# digital_noise_gen.net
KiCad netlist of a schematic drawn in EAGLE
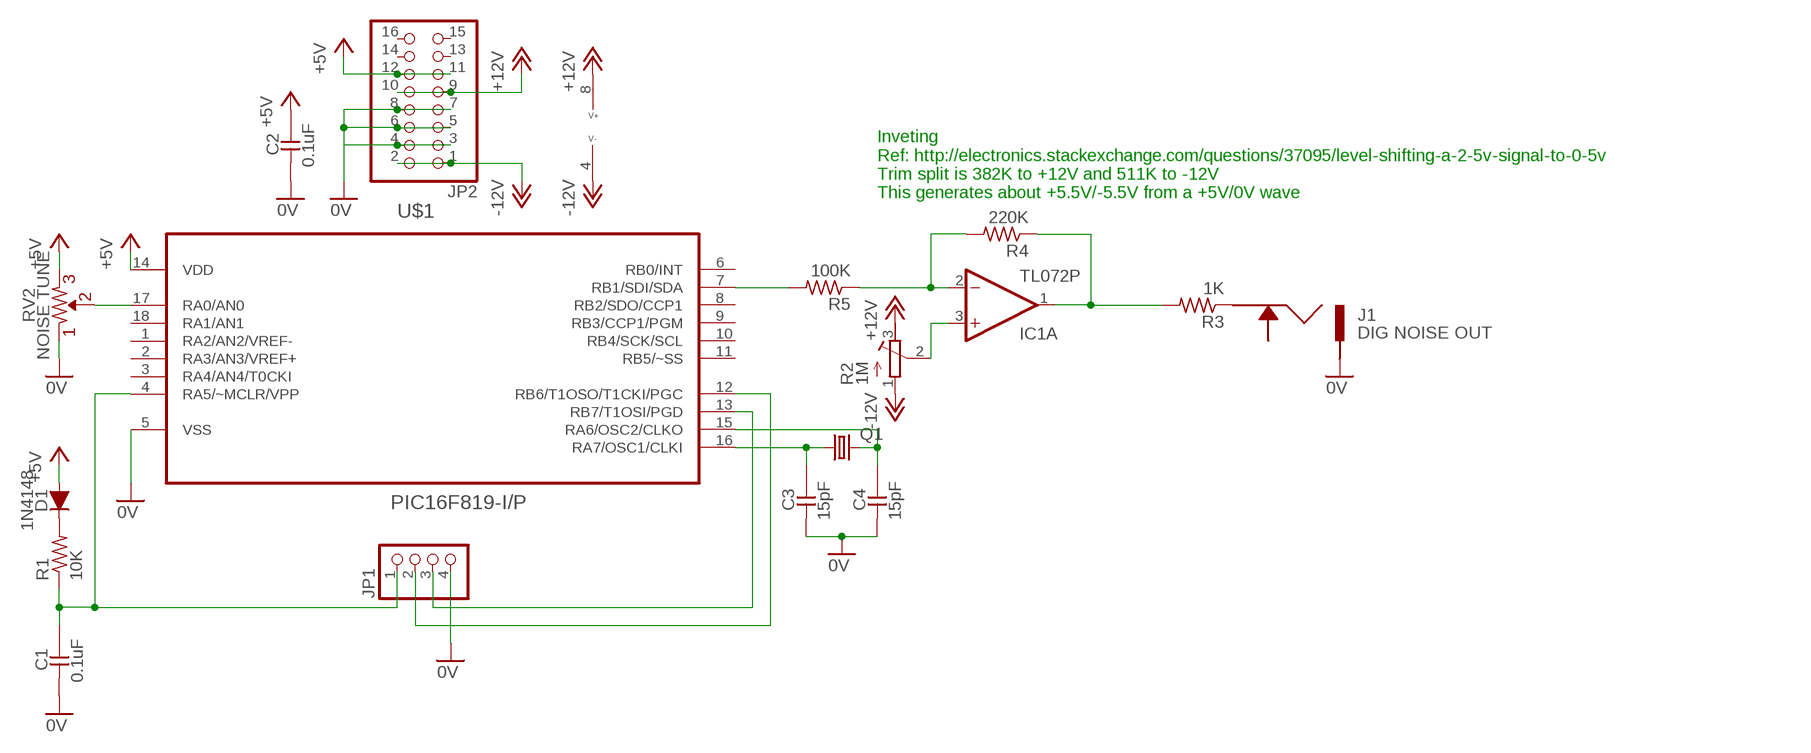
[diagram p0: schematic, sheet 1]

(export (version "E")
  (design (tool "Eeschema 10.0.6"))
  (components
    (comp (ref "C1")
      (value "0.1uF")
      (footprint "eagle-import:C025-024X044")
      (libsource (lib "eagle-import") (part "CC-US025-024X044"))
    )
    (comp (ref "C2")
      (value "0.1uF")
      (footprint "eagle-import:C025-024X044")
      (libsource (lib "eagle-import") (part "CC-US025-024X044"))
    )
    (comp (ref "C3")
      (value "15pF")
      (footprint "eagle-import:C025-024X044")
      (libsource (lib "eagle-import") (part "CC-US025-024X044"))
    )
    (comp (ref "C4")
      (value "15pF")
      (footprint "eagle-import:C025-024X044")
      (libsource (lib "eagle-import") (part "CC-US025-024X044"))
    )
    (comp (ref "D1")
      (value "1N4148")
      (footprint "eagle-import:DO35-7")
      (libsource (lib "eagle-import") (part "1N4148"))
    )
    (comp (ref "IC1")
      (value "TL072P")
      (footprint "eagle-import:DIL08")
      (libsource (lib "eagle-import") (part "TL072P"))
    )
    (comp (ref "J1")
      (value "DIG NOISE OUT")
      (footprint "eagle-import:ACJM-MV35-2S")
      (libsource (lib "eagle-import") (part "ACJM-MV35-2S"))
    )
    (comp (ref "JP1")
      (value "PINHD-1X4")
      (footprint "eagle-import:1X04")
      (libsource (lib "eagle-import") (part "PINHD-1X4"))
    )
    (comp (ref "JP2")
      (value "PINHD-2X8")
      (footprint "eagle-import:2X08")
      (libsource (lib "eagle-import") (part "PINHD-2X8"))
    )
    (comp (ref "Q1")
      (value "CRYSTALHC49S")
      (footprint "eagle-import:HC49_S")
      (libsource (lib "eagle-import") (part "CRYSTALHC49S"))
    )
    (comp (ref "R1")
      (value "10K")
      (footprint "eagle-import:0207_7")
      (libsource (lib "eagle-import") (part "R-US_0207/7"))
    )
    (comp (ref "R2")
      (value "1M")
      (footprint "eagle-import:RTRIM3339P")
      (libsource (lib "eagle-import") (part "R-TRIMM3339P"))
    )
    (comp (ref "R3")
      (value "1K")
      (footprint "eagle-import:0207_7")
      (libsource (lib "eagle-import") (part "R-US_0207/7"))
    )
    (comp (ref "R4")
      (value "220K")
      (footprint "eagle-import:0207_7")
      (libsource (lib "eagle-import") (part "R-US_0207/7"))
    )
    (comp (ref "R5")
      (value "100K")
      (footprint "eagle-import:0207_7")
      (libsource (lib "eagle-import") (part "R-US_0207/7"))
    )
    (comp (ref "RV2")
      (value "NOISE TUNE")
      (footprint "eagle-import:R-VAR")
      (libsource (lib "eagle-import") (part "R-VAR"))
    )
    (comp (ref "U$1")
      (value "PIC16F819-I/P")
      (footprint "eagle-import:DIP254P762X432-18")
      (libsource (lib "eagle-import") (part "PIC16F819-I/P"))
    )
  )
  (nets
    (net (code "1") (name "+5V") (class "Default")
      (node (ref "C2") (pin "1") (pinfunction "1_1") (pintype "passive"))
      (node (ref "D1") (pin "A") (pinfunction "A_A") (pintype "passive"))
      (node (ref "JP2") (pin "11") (pinfunction "11_11") (pintype "passive"))
      (node (ref "JP2") (pin "12") (pinfunction "12_12") (pintype "passive"))
      (node (ref "RV2") (pin "R2") (pinfunction "2_R2") (pintype "passive"))
      (node (ref "U$1") (pin "14") (pinfunction "VDD_14") (pintype "power_in"))
    )
    (net (code "2") (name "+12V") (class "Default")
      (node (ref "IC1") (pin "8") (pinfunction "V+_8") (pintype "power_in"))
      (node (ref "JP2") (pin "10") (pinfunction "10_10") (pintype "passive"))
      (node (ref "JP2") (pin "9") (pinfunction "9_9") (pintype "passive"))
      (node (ref "R2") (pin "3") (pinfunction "E_3") (pintype "passive"))
    )
    (net (code "3") (name "-12V") (class "Default")
      (node (ref "IC1") (pin "4") (pinfunction "V-_4") (pintype "power_in"))
      (node (ref "JP2") (pin "1") (pinfunction "1_1") (pintype "passive"))
      (node (ref "JP2") (pin "2") (pinfunction "2_2") (pintype "passive"))
      (node (ref "R2") (pin "1") (pinfunction "A_1") (pintype "passive"))
    )
    (net (code "4") (name "0V") (class "Default")
      (node (ref "C1") (pin "2") (pinfunction "2_2") (pintype "passive"))
      (node (ref "C2") (pin "2") (pinfunction "2_2") (pintype "passive"))
      (node (ref "C3") (pin "2") (pinfunction "2_2") (pintype "passive"))
      (node (ref "C4") (pin "2") (pinfunction "2_2") (pintype "passive"))
      (node (ref "J1") (pin "P$1") (pinfunction "P$1_P$1") (pintype "bidirectional"))
      (node (ref "JP1") (pin "4") (pinfunction "4_4") (pintype "passive"))
      (node (ref "JP2") (pin "3") (pinfunction "3_3") (pintype "passive"))
      (node (ref "JP2") (pin "4") (pinfunction "4_4") (pintype "passive"))
      (node (ref "JP2") (pin "5") (pinfunction "5_5") (pintype "passive"))
      (node (ref "JP2") (pin "6") (pinfunction "6_6") (pintype "passive"))
      (node (ref "JP2") (pin "7") (pinfunction "7_7") (pintype "passive"))
      (node (ref "JP2") (pin "8") (pinfunction "8_8") (pintype "passive"))
      (node (ref "RV2") (pin "R1") (pinfunction "1_R1") (pintype "passive"))
      (node (ref "U$1") (pin "5") (pinfunction "VSS_5") (pintype "passive"))
    )
    (net (code "5") (name "Net-(D1-PadC)") (class "Default")
      (node (ref "D1") (pin "C") (pinfunction "C_C") (pintype "passive"))
      (node (ref "R1") (pin "2") (pinfunction "2_2") (pintype "passive"))
    )
    (net (code "6") (name "Net-(IC1A-+IN)") (class "Default")
      (node (ref "IC1") (pin "3") (pinfunction "+IN_3") (pintype "input"))
      (node (ref "R2") (pin "2") (pinfunction "S_2") (pintype "passive"))
    )
    (net (code "7") (name "Net-(IC1A--IN)") (class "Default")
      (node (ref "IC1") (pin "2") (pinfunction "-IN_2") (pintype "input"))
      (node (ref "R4") (pin "2") (pinfunction "2_2") (pintype "passive"))
      (node (ref "R5") (pin "1") (pinfunction "1_1") (pintype "passive"))
    )
    (net (code "8") (name "Net-(IC1A-OUT)") (class "Default")
      (node (ref "IC1") (pin "1") (pinfunction "OUT_1") (pintype "output"))
      (node (ref "R3") (pin "2") (pinfunction "2_2") (pintype "passive"))
      (node (ref "R4") (pin "1") (pinfunction "1_1") (pintype "passive"))
    )
    (net (code "9") (name "Net-(J1-P$2)") (class "Default")
      (node (ref "J1") (pin "P$3") (pinfunction "P$2_P$3") (pintype "bidirectional"))
      (node (ref "R3") (pin "1") (pinfunction "1_1") (pintype "passive"))
    )
    (net (code "10") (name "Net-(RV2-P$1)") (class "Default")
      (node (ref "RV2") (pin "VAR") (pinfunction "P$1_VAR") (pintype "passive"))
      (node (ref "U$1") (pin "17") (pinfunction "RA0/AN0_17") (pintype "bidirectional"))
    )
    (net (code "11") (name "Net-(U$1-RA5{slash}~{MCLR{slash}VPP})") (class "Default")
      (node (ref "C1") (pin "1") (pinfunction "1_1") (pintype "passive"))
      (node (ref "JP1") (pin "1") (pinfunction "1_1") (pintype "passive"))
      (node (ref "R1") (pin "1") (pinfunction "1_1") (pintype "passive"))
      (node (ref "U$1") (pin "4") (pinfunction "RA5/~{MCLR/VPP}_4") (pintype "input"))
    )
    (net (code "12") (name "Net-(U$1-RA6{slash}OSC2{slash}CLKO)") (class "Default")
      (node (ref "C4") (pin "1") (pinfunction "1_1") (pintype "passive"))
      (node (ref "Q1") (pin "2") (pinfunction "2_2") (pintype "passive"))
      (node (ref "U$1") (pin "15") (pinfunction "RA6/OSC2/CLKO_15") (pintype "bidirectional"))
    )
    (net (code "13") (name "Net-(U$1-RA7{slash}OSC1{slash}CLKI)") (class "Default")
      (node (ref "C3") (pin "1") (pinfunction "1_1") (pintype "passive"))
      (node (ref "Q1") (pin "1") (pinfunction "1_1") (pintype "passive"))
      (node (ref "U$1") (pin "16") (pinfunction "RA7/OSC1/CLKI_16") (pintype "bidirectional"))
    )
    (net (code "14") (name "Net-(U$1-RB1{slash}SDI{slash}SDA)") (class "Default")
      (node (ref "R5") (pin "2") (pinfunction "2_2") (pintype "passive"))
      (node (ref "U$1") (pin "7") (pinfunction "RB1/SDI/SDA_7") (pintype "bidirectional"))
    )
    (net (code "15") (name "Net-(U$1-RB6{slash}T1OSO{slash}T1CKI{slash}PGC)") (class "Default")
      (node (ref "JP1") (pin "2") (pinfunction "2_2") (pintype "passive"))
      (node (ref "U$1") (pin "12") (pinfunction "RB6/T1OSO/T1CKI/PGC_12") (pintype "bidirectional"))
    )
    (net (code "16") (name "Net-(U$1-RB7{slash}T1OSI{slash}PGD)") (class "Default")
      (node (ref "JP1") (pin "3") (pinfunction "3_3") (pintype "passive"))
      (node (ref "U$1") (pin "13") (pinfunction "RB7/T1OSI/PGD_13") (pintype "bidirectional"))
    )
    (net (code "17") (name "unconnected-(J1-P$3-PadP$2)") (class "Default")
      (node (ref "J1") (pin "P$2") (pinfunction "P$3_P$2") (pintype "bidirectional"))
    )
    (net (code "18") (name "unconnected-(JP2-Pad13)") (class "Default")
      (node (ref "JP2") (pin "13") (pinfunction "13_13") (pintype "passive"))
    )
    (net (code "19") (name "unconnected-(JP2-Pad14)") (class "Default")
      (node (ref "JP2") (pin "14") (pinfunction "14_14") (pintype "passive"))
    )
    (net (code "20") (name "unconnected-(JP2-Pad15)") (class "Default")
      (node (ref "JP2") (pin "15") (pinfunction "15_15") (pintype "passive"))
    )
    (net (code "21") (name "unconnected-(JP2-Pad16)") (class "Default")
      (node (ref "JP2") (pin "16") (pinfunction "16_16") (pintype "passive"))
    )
    (net (code "22") (name "unconnected-(U$1-RA1{slash}AN1-Pad18)") (class "Default")
      (node (ref "U$1") (pin "18") (pinfunction "RA1/AN1_18") (pintype "bidirectional"))
    )
    (net (code "23") (name "unconnected-(U$1-RA2{slash}AN2{slash}VREF--Pad1)") (class "Default")
      (node (ref "U$1") (pin "1") (pinfunction "RA2/AN2/VREF-_1") (pintype "bidirectional"))
    )
    (net (code "24") (name "unconnected-(U$1-RA3{slash}AN3{slash}VREF+-Pad2)") (class "Default")
      (node (ref "U$1") (pin "2") (pinfunction "RA3/AN3/VREF+_2") (pintype "bidirectional"))
    )
    (net (code "25") (name "unconnected-(U$1-RA4{slash}AN4{slash}T0CKI-Pad3)") (class "Default")
      (node (ref "U$1") (pin "3") (pinfunction "RA4/AN4/T0CKI_3") (pintype "bidirectional"))
    )
    (net (code "26") (name "unconnected-(U$1-RB0{slash}INT-Pad6)") (class "Default")
      (node (ref "U$1") (pin "6") (pinfunction "RB0/INT_6") (pintype "bidirectional"))
    )
    (net (code "27") (name "unconnected-(U$1-RB2{slash}SDO{slash}CCP1-Pad8)") (class "Default")
      (node (ref "U$1") (pin "8") (pinfunction "RB2/SDO/CCP1_8") (pintype "bidirectional"))
    )
    (net (code "28") (name "unconnected-(U$1-RB3{slash}CCP1{slash}PGM-Pad9)") (class "Default")
      (node (ref "U$1") (pin "9") (pinfunction "RB3/CCP1/PGM_9") (pintype "bidirectional"))
    )
    (net (code "29") (name "unconnected-(U$1-RB4{slash}SCK{slash}SCL-Pad10)") (class "Default")
      (node (ref "U$1") (pin "10") (pinfunction "RB4/SCK/SCL_10") (pintype "bidirectional"))
    )
    (net (code "30") (name "unconnected-(U$1-RB5{slash}~{SS}-Pad11)") (class "Default")
      (node (ref "U$1") (pin "11") (pinfunction "RB5/~{SS}_11") (pintype "bidirectional"))
    )
  )
)
